# BrainTrainer.net
KiCad netlist of a schematic drawn in EAGLE
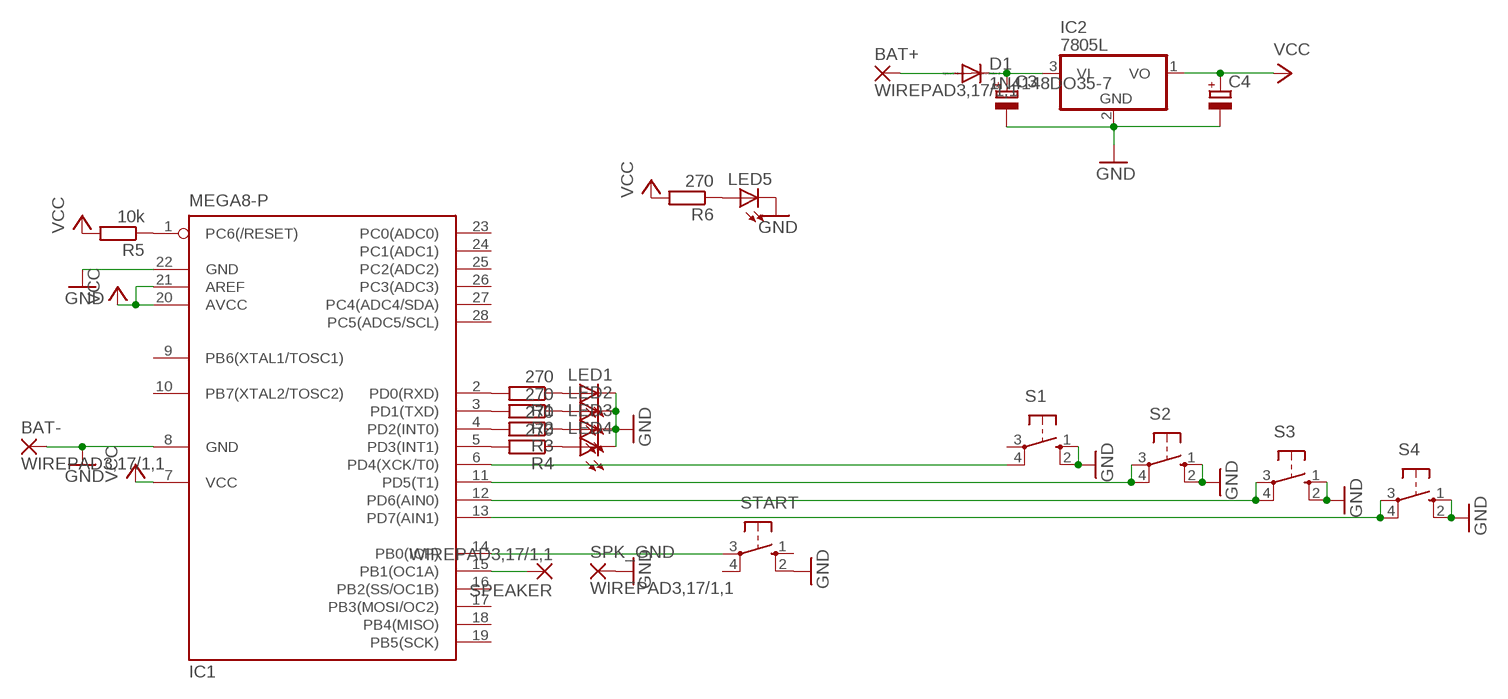
[diagram p0: schematic, sheet 1]

(export (version "E")
  (design (tool "Eeschema 10.0.6"))
  (components
    (comp (ref "BAT+")
      (value "WIREPAD3,17/1,1")
      (footprint "eagle-import:3,17_1,1")
      (libsource (lib "eagle-import") (part "WIREPAD3,17/1,1"))
    )
    (comp (ref "BAT-")
      (value "WIREPAD3,17/1,1")
      (footprint "eagle-import:3,17_1,1")
      (libsource (lib "eagle-import") (part "WIREPAD3,17/1,1"))
    )
    (comp (ref "C3")
      (value "CPOL-EUE2,5-6E")
      (footprint "eagle-import:E2,5-6E")
      (libsource (lib "eagle-import") (part "CPOL-EUE2,5-6E"))
    )
    (comp (ref "C4")
      (value "CPOL-EUE2,5-6E")
      (footprint "eagle-import:E2,5-6E")
      (libsource (lib "eagle-import") (part "CPOL-EUE2,5-6E"))
    )
    (comp (ref "D1")
      (value "1N4148DO35-7")
      (footprint "eagle-import:DO35-7")
      (libsource (lib "eagle-import") (part "1N4148DO35-7"))
    )
    (comp (ref "IC1")
      (value "MEGA8-P")
      (footprint "eagle-import:DIL28-3")
      (libsource (lib "eagle-import") (part "MEGA8-P"))
    )
    (comp (ref "IC2")
      (value "7805L")
      (footprint "eagle-import:TO92")
      (libsource (lib "eagle-import") (part "78L05"))
    )
    (comp (ref "LED1")
      (value "LED5MM")
      (footprint "eagle-import:LED5MM")
      (libsource (lib "eagle-import") (part "LED5MM"))
    )
    (comp (ref "LED2")
      (value "LED5MM")
      (footprint "eagle-import:LED5MM")
      (libsource (lib "eagle-import") (part "LED5MM"))
    )
    (comp (ref "LED3")
      (value "LED5MM")
      (footprint "eagle-import:LED5MM")
      (libsource (lib "eagle-import") (part "LED5MM"))
    )
    (comp (ref "LED4")
      (value "LED5MM")
      (footprint "eagle-import:LED5MM")
      (libsource (lib "eagle-import") (part "LED5MM"))
    )
    (comp (ref "LED5")
      (value "LED5MM")
      (footprint "eagle-import:LED5MM")
      (libsource (lib "eagle-import") (part "LED5MM"))
    )
    (comp (ref "R1")
      (value "270")
      (footprint "eagle-import:0207_7")
      (libsource (lib "eagle-import") (part "R-EU_0207/7"))
    )
    (comp (ref "R2")
      (value "270")
      (footprint "eagle-import:0207_7")
      (libsource (lib "eagle-import") (part "R-EU_0207/7"))
    )
    (comp (ref "R3")
      (value "270")
      (footprint "eagle-import:0207_7")
      (libsource (lib "eagle-import") (part "R-EU_0207/7"))
    )
    (comp (ref "R4")
      (value "270")
      (footprint "eagle-import:0207_7")
      (libsource (lib "eagle-import") (part "R-EU_0207/7"))
    )
    (comp (ref "R5")
      (value "10k")
      (footprint "eagle-import:0207_7")
      (libsource (lib "eagle-import") (part "R-EU_0207/7"))
    )
    (comp (ref "R6")
      (value "270")
      (footprint "eagle-import:0207_7")
      (libsource (lib "eagle-import") (part "R-EU_0207/7"))
    )
    (comp (ref "S1")
      (value "10-XX")
      (footprint "eagle-import:B3F-10XX")
      (fields (field (name "MPN") "B3F-1000"))
      (libsource (lib "eagle-import") (part "10-XX"))
    )
    (comp (ref "S2")
      (value "10-XX")
      (footprint "eagle-import:B3F-10XX")
      (fields (field (name "MPN") "B3F-1000"))
      (libsource (lib "eagle-import") (part "10-XX"))
    )
    (comp (ref "S3")
      (value "10-XX")
      (footprint "eagle-import:B3F-10XX")
      (fields (field (name "MPN") "B3F-1000"))
      (libsource (lib "eagle-import") (part "10-XX"))
    )
    (comp (ref "S4")
      (value "10-XX")
      (footprint "eagle-import:B3F-10XX")
      (fields (field (name "MPN") "B3F-1000"))
      (libsource (lib "eagle-import") (part "10-XX"))
    )
    (comp (ref "SPEAKER")
      (value "WIREPAD3,17/1,1")
      (footprint "eagle-import:3,17_1,1")
      (libsource (lib "eagle-import") (part "WIREPAD3,17/1,1"))
    )
    (comp (ref "SPK_GND")
      (value "WIREPAD3,17/1,1")
      (footprint "eagle-import:3,17_1,1")
      (libsource (lib "eagle-import") (part "WIREPAD3,17/1,1"))
    )
    (comp (ref "START")
      (value "10-XX")
      (footprint "eagle-import:B3F-10XX")
      (fields (field (name "MPN") "B3F-1000"))
      (libsource (lib "eagle-import") (part "10-XX"))
    )
  )
  (nets
    (net (code "1") (name "GND") (class "Default")
      (node (ref "BAT-") (pin "1") (pinfunction "P_1") (pintype "passive"))
      (node (ref "C3") (pin "-") (pinfunction "-_-") (pintype "passive"))
      (node (ref "C4") (pin "-") (pinfunction "-_-") (pintype "passive"))
      (node (ref "IC1") (pin "22") (pinfunction "GND_22") (pintype "power_in"))
      (node (ref "IC1") (pin "8") (pinfunction "GND_8") (pintype "power_in"))
      (node (ref "IC2") (pin "2") (pinfunction "GND_2") (pintype "passive"))
      (node (ref "LED1") (pin "K") (pinfunction "C_K") (pintype "passive"))
      (node (ref "LED2") (pin "K") (pinfunction "C_K") (pintype "passive"))
      (node (ref "LED3") (pin "K") (pinfunction "C_K") (pintype "passive"))
      (node (ref "LED4") (pin "K") (pinfunction "C_K") (pintype "passive"))
      (node (ref "LED5") (pin "K") (pinfunction "C_K") (pintype "passive"))
      (node (ref "S1") (pin "1") (pinfunction "S_1") (pintype "passive"))
      (node (ref "S1") (pin "2") (pinfunction "S1_2") (pintype "passive"))
      (node (ref "S2") (pin "1") (pinfunction "S_1") (pintype "passive"))
      (node (ref "S2") (pin "2") (pinfunction "S1_2") (pintype "passive"))
      (node (ref "S3") (pin "1") (pinfunction "S_1") (pintype "passive"))
      (node (ref "S3") (pin "2") (pinfunction "S1_2") (pintype "passive"))
      (node (ref "S4") (pin "1") (pinfunction "S_1") (pintype "passive"))
      (node (ref "S4") (pin "2") (pinfunction "S1_2") (pintype "passive"))
      (node (ref "SPK_GND") (pin "1") (pinfunction "P_1") (pintype "passive"))
      (node (ref "START") (pin "2") (pinfunction "S1_2") (pintype "passive"))
    )
    (net (code "2") (name "Net-(BAT+-P)") (class "Default")
      (node (ref "BAT+") (pin "1") (pinfunction "P_1") (pintype "passive"))
      (node (ref "D1") (pin "A") (pinfunction "A_A") (pintype "passive"))
    )
    (net (code "3") (name "Net-(IC1-PB0(ICP))") (class "Default")
      (node (ref "IC1") (pin "14") (pinfunction "PB0(ICP)_14") (pintype "bidirectional"))
      (node (ref "START") (pin "3") (pinfunction "P_3") (pintype "passive"))
    )
    (net (code "4") (name "Net-(IC1-PB1(OC1A))") (class "Default")
      (node (ref "IC1") (pin "15") (pinfunction "PB1(OC1A)_15") (pintype "bidirectional"))
      (node (ref "SPEAKER") (pin "1") (pinfunction "P_1") (pintype "passive"))
    )
    (net (code "5") (name "Net-(IC1-PC6({slash}RESET))") (class "Default")
      (node (ref "IC1") (pin "1") (pinfunction "PC6(/RESET)_1") (pintype "bidirectional"))
      (node (ref "R5") (pin "1") (pinfunction "1_1") (pintype "passive"))
    )
    (net (code "6") (name "Net-(IC1-PD0(RXD))") (class "Default")
      (node (ref "IC1") (pin "2") (pinfunction "PD0(RXD)_2") (pintype "bidirectional"))
      (node (ref "R1") (pin "2") (pinfunction "2_2") (pintype "passive"))
    )
    (net (code "7") (name "Net-(IC1-PD1(TXD))") (class "Default")
      (node (ref "IC1") (pin "3") (pinfunction "PD1(TXD)_3") (pintype "bidirectional"))
      (node (ref "R2") (pin "2") (pinfunction "2_2") (pintype "passive"))
    )
    (net (code "8") (name "Net-(IC1-PD2(INT0))") (class "Default")
      (node (ref "IC1") (pin "4") (pinfunction "PD2(INT0)_4") (pintype "bidirectional"))
      (node (ref "R3") (pin "2") (pinfunction "2_2") (pintype "passive"))
    )
    (net (code "9") (name "Net-(IC1-PD3(INT1))") (class "Default")
      (node (ref "IC1") (pin "5") (pinfunction "PD3(INT1)_5") (pintype "bidirectional"))
      (node (ref "R4") (pin "2") (pinfunction "2_2") (pintype "passive"))
    )
    (net (code "10") (name "Net-(IC1-PD4(XCK{slash}T0))") (class "Default")
      (node (ref "IC1") (pin "6") (pinfunction "PD4(XCK/T0)_6") (pintype "bidirectional"))
      (node (ref "S1") (pin "4") (pinfunction "P1_4") (pintype "passive"))
    )
    (net (code "11") (name "Net-(IC1-PD5(T1))") (class "Default")
      (node (ref "IC1") (pin "11") (pinfunction "PD5(T1)_11") (pintype "bidirectional"))
      (node (ref "S2") (pin "3") (pinfunction "P_3") (pintype "passive"))
      (node (ref "S2") (pin "4") (pinfunction "P1_4") (pintype "passive"))
    )
    (net (code "12") (name "Net-(IC1-PD6(AIN0))") (class "Default")
      (node (ref "IC1") (pin "12") (pinfunction "PD6(AIN0)_12") (pintype "bidirectional"))
      (node (ref "S3") (pin "3") (pinfunction "P_3") (pintype "passive"))
      (node (ref "S3") (pin "4") (pinfunction "P1_4") (pintype "passive"))
    )
    (net (code "13") (name "Net-(IC1-PD7(AIN1))") (class "Default")
      (node (ref "IC1") (pin "13") (pinfunction "PD7(AIN1)_13") (pintype "bidirectional"))
      (node (ref "S4") (pin "3") (pinfunction "P_3") (pintype "passive"))
      (node (ref "S4") (pin "4") (pinfunction "P1_4") (pintype "passive"))
    )
    (net (code "14") (name "Net-(IC2-VI)") (class "Default")
      (node (ref "C3") (pin "+") (pinfunction "+_+") (pintype "passive"))
      (node (ref "D1") (pin "C") (pinfunction "C_C") (pintype "passive"))
      (node (ref "IC2") (pin "3") (pinfunction "VI_3") (pintype "input"))
    )
    (net (code "15") (name "Net-(LED1-PadA)") (class "Default")
      (node (ref "LED1") (pin "A") (pinfunction "A_A") (pintype "passive"))
      (node (ref "R1") (pin "1") (pinfunction "1_1") (pintype "passive"))
    )
    (net (code "16") (name "Net-(LED2-PadA)") (class "Default")
      (node (ref "LED2") (pin "A") (pinfunction "A_A") (pintype "passive"))
      (node (ref "R2") (pin "1") (pinfunction "1_1") (pintype "passive"))
    )
    (net (code "17") (name "Net-(LED3-PadA)") (class "Default")
      (node (ref "LED3") (pin "A") (pinfunction "A_A") (pintype "passive"))
      (node (ref "R3") (pin "1") (pinfunction "1_1") (pintype "passive"))
    )
    (net (code "18") (name "Net-(LED4-PadA)") (class "Default")
      (node (ref "LED4") (pin "A") (pinfunction "A_A") (pintype "passive"))
      (node (ref "R4") (pin "1") (pinfunction "1_1") (pintype "passive"))
    )
    (net (code "19") (name "Net-(LED5-PadA)") (class "Default")
      (node (ref "LED5") (pin "A") (pinfunction "A_A") (pintype "passive"))
      (node (ref "R6") (pin "1") (pinfunction "1_1") (pintype "passive"))
    )
    (net (code "20") (name "VCC") (class "Default")
      (node (ref "C4") (pin "+") (pinfunction "+_+") (pintype "passive"))
      (node (ref "IC1") (pin "20") (pinfunction "AVCC_20") (pintype "power_in"))
      (node (ref "IC1") (pin "21") (pinfunction "AREF_21") (pintype "passive"))
      (node (ref "IC1") (pin "7") (pinfunction "VCC_7") (pintype "power_in"))
      (node (ref "IC2") (pin "1") (pinfunction "VO_1") (pintype "passive"))
      (node (ref "R5") (pin "2") (pinfunction "2_2") (pintype "passive"))
      (node (ref "R6") (pin "2") (pinfunction "2_2") (pintype "passive"))
    )
    (net (code "21") (name "unconnected-(IC1-PB2(SS{slash}OC1B)-Pad16)") (class "Default")
      (node (ref "IC1") (pin "16") (pinfunction "PB2(SS/OC1B)_16") (pintype "bidirectional"))
    )
    (net (code "22") (name "unconnected-(IC1-PB3(MOSI{slash}OC2)-Pad17)") (class "Default")
      (node (ref "IC1") (pin "17") (pinfunction "PB3(MOSI/OC2)_17") (pintype "bidirectional"))
    )
    (net (code "23") (name "unconnected-(IC1-PB4(MISO)-Pad18)") (class "Default")
      (node (ref "IC1") (pin "18") (pinfunction "PB4(MISO)_18") (pintype "bidirectional"))
    )
    (net (code "24") (name "unconnected-(IC1-PB5(SCK)-Pad19)") (class "Default")
      (node (ref "IC1") (pin "19") (pinfunction "PB5(SCK)_19") (pintype "bidirectional"))
    )
    (net (code "25") (name "unconnected-(IC1-PB6(XTAL1{slash}TOSC1)-Pad9)") (class "Default")
      (node (ref "IC1") (pin "9") (pinfunction "PB6(XTAL1/TOSC1)_9") (pintype "bidirectional"))
    )
    (net (code "26") (name "unconnected-(IC1-PB7(XTAL2{slash}TOSC2)-Pad10)") (class "Default")
      (node (ref "IC1") (pin "10") (pinfunction "PB7(XTAL2/TOSC2)_10") (pintype "bidirectional"))
    )
    (net (code "27") (name "unconnected-(IC1-PC0(ADC0)-Pad23)") (class "Default")
      (node (ref "IC1") (pin "23") (pinfunction "PC0(ADC0)_23") (pintype "bidirectional"))
    )
    (net (code "28") (name "unconnected-(IC1-PC1(ADC1)-Pad24)") (class "Default")
      (node (ref "IC1") (pin "24") (pinfunction "PC1(ADC1)_24") (pintype "bidirectional"))
    )
    (net (code "29") (name "unconnected-(IC1-PC2(ADC2)-Pad25)") (class "Default")
      (node (ref "IC1") (pin "25") (pinfunction "PC2(ADC2)_25") (pintype "bidirectional"))
    )
    (net (code "30") (name "unconnected-(IC1-PC3(ADC3)-Pad26)") (class "Default")
      (node (ref "IC1") (pin "26") (pinfunction "PC3(ADC3)_26") (pintype "bidirectional"))
    )
    (net (code "31") (name "unconnected-(IC1-PC4(ADC4{slash}SDA)-Pad27)") (class "Default")
      (node (ref "IC1") (pin "27") (pinfunction "PC4(ADC4/SDA)_27") (pintype "bidirectional"))
    )
    (net (code "32") (name "unconnected-(IC1-PC5(ADC5{slash}SCL)-Pad28)") (class "Default")
      (node (ref "IC1") (pin "28") (pinfunction "PC5(ADC5/SCL)_28") (pintype "bidirectional"))
    )
    (net (code "33") (name "unconnected-(S1-P-Pad3)") (class "Default")
      (node (ref "S1") (pin "3") (pinfunction "P_3") (pintype "passive"))
    )
    (net (code "34") (name "unconnected-(START-P1-Pad4)") (class "Default")
      (node (ref "START") (pin "4") (pinfunction "P1_4") (pintype "passive"))
    )
    (net (code "35") (name "unconnected-(START-S-Pad1)") (class "Default")
      (node (ref "START") (pin "1") (pinfunction "S_1") (pintype "passive"))
    )
  )
)
